# StarLiteMain.net
KiCad netlist of a schematic drawn in EAGLE
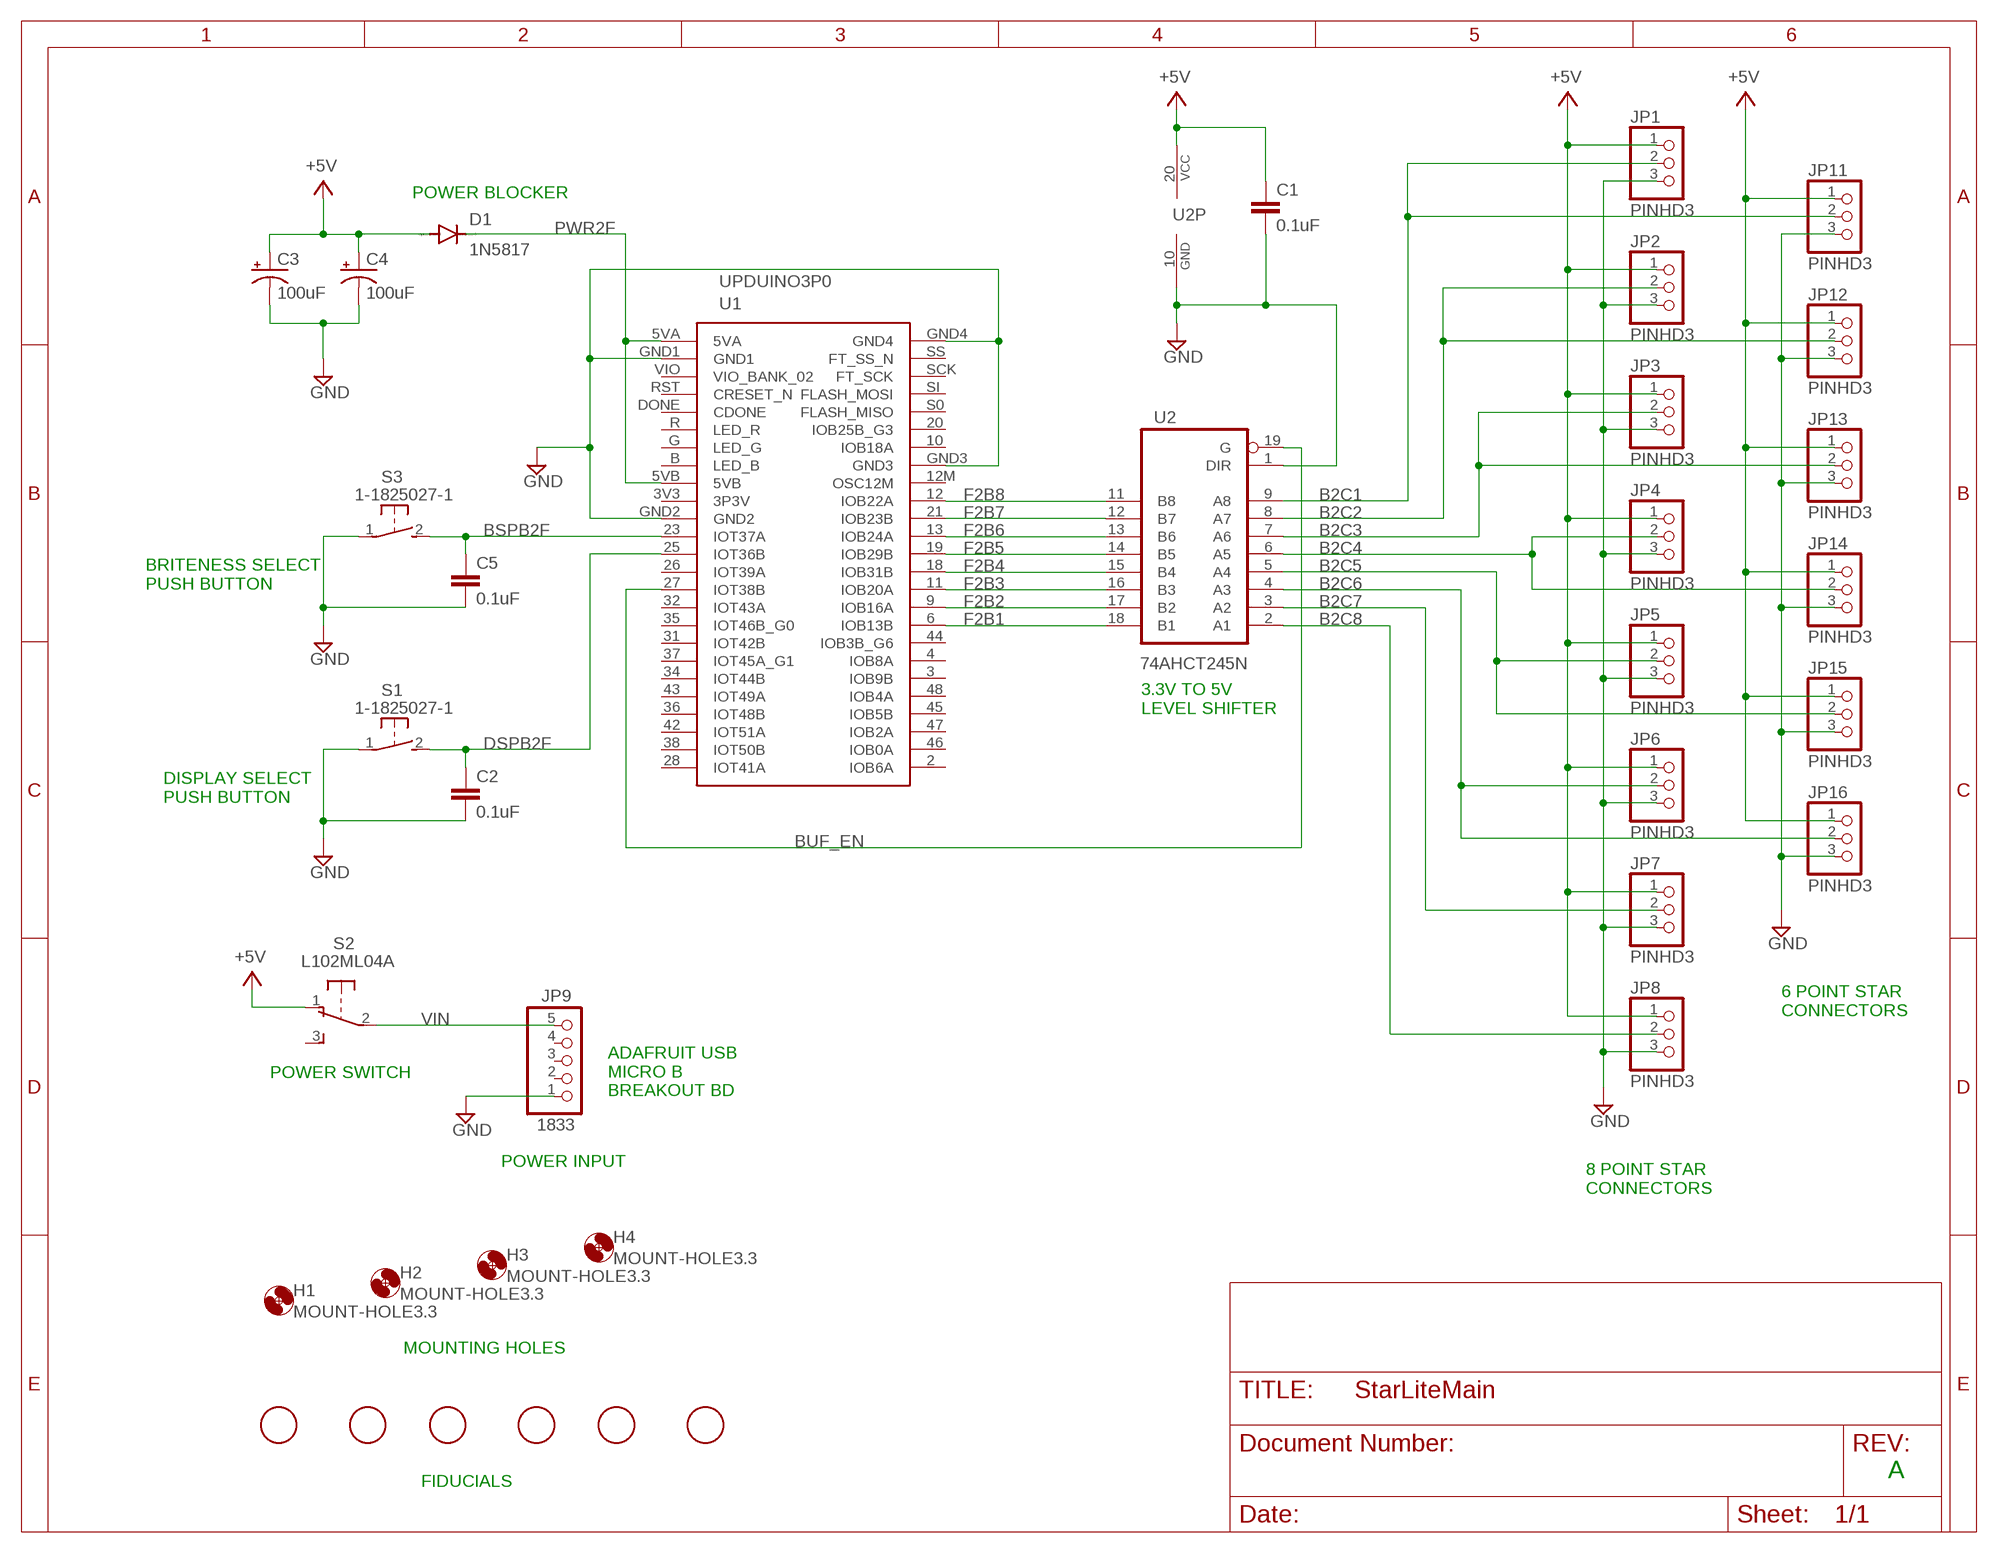
[diagram p0: schematic, sheet 1]

(export (version "E")
  (design (tool "Eeschema 10.0.6"))
  (components
    (comp (ref "C1")
      (value "0.1uF")
      (footprint "eagle-import:C2.5-3")
      (libsource (lib "eagle-import") (part "C2,5-3"))
    )
    (comp (ref "C2")
      (value "0.1uF")
      (footprint "eagle-import:C2.5-3")
      (libsource (lib "eagle-import") (part "C2,5-3"))
    )
    (comp (ref "C3")
      (value "100uF")
      (footprint "eagle-import:E2,5-6")
      (libsource (lib "eagle-import") (part "CPOL-USE2.5-6"))
    )
    (comp (ref "C4")
      (value "100uF")
      (footprint "eagle-import:E2,5-6")
      (libsource (lib "eagle-import") (part "CPOL-USE2.5-6"))
    )
    (comp (ref "C5")
      (value "0.1uF")
      (footprint "eagle-import:C2.5-3")
      (libsource (lib "eagle-import") (part "C2,5-3"))
    )
    (comp (ref "D1")
      (value "1N5817")
      (footprint "eagle-import:DO41-10")
      (libsource (lib "eagle-import") (part "DIODE-DO41-10"))
    )
    (comp (ref "H1")
      (value "MOUNT-HOLE3.3")
      (footprint "eagle-import:3,3")
      (libsource (lib "eagle-import") (part "MOUNT-HOLE3.3"))
    )
    (comp (ref "H2")
      (value "MOUNT-HOLE3.3")
      (footprint "eagle-import:3,3")
      (libsource (lib "eagle-import") (part "MOUNT-HOLE3.3"))
    )
    (comp (ref "H3")
      (value "MOUNT-HOLE3.3")
      (footprint "eagle-import:3,3")
      (libsource (lib "eagle-import") (part "MOUNT-HOLE3.3"))
    )
    (comp (ref "H4")
      (value "MOUNT-HOLE3.3")
      (footprint "eagle-import:3,3")
      (libsource (lib "eagle-import") (part "MOUNT-HOLE3.3"))
    )
    (comp (ref "JP1")
      (value "PINHD3")
      (footprint "eagle-import:1X03_50MIL")
      (libsource (lib "eagle-import") (part "PINHD-1X31X03_50"))
    )
    (comp (ref "JP2")
      (value "PINHD3")
      (footprint "eagle-import:1X03_50MIL")
      (libsource (lib "eagle-import") (part "PINHD-1X31X03_50"))
    )
    (comp (ref "JP3")
      (value "PINHD3")
      (footprint "eagle-import:1X03_50MIL")
      (libsource (lib "eagle-import") (part "PINHD-1X31X03_50"))
    )
    (comp (ref "JP4")
      (value "PINHD3")
      (footprint "eagle-import:1X03_50MIL")
      (libsource (lib "eagle-import") (part "PINHD-1X31X03_50"))
    )
    (comp (ref "JP5")
      (value "PINHD3")
      (footprint "eagle-import:1X03_50MIL")
      (libsource (lib "eagle-import") (part "PINHD-1X31X03_50"))
    )
    (comp (ref "JP6")
      (value "PINHD3")
      (footprint "eagle-import:1X03_50MIL")
      (libsource (lib "eagle-import") (part "PINHD-1X31X03_50"))
    )
    (comp (ref "JP7")
      (value "PINHD3")
      (footprint "eagle-import:1X03_50MIL")
      (libsource (lib "eagle-import") (part "PINHD-1X31X03_50"))
    )
    (comp (ref "JP8")
      (value "PINHD3")
      (footprint "eagle-import:1X03_50MIL")
      (libsource (lib "eagle-import") (part "PINHD-1X31X03_50"))
    )
    (comp (ref "JP9")
      (value "1833")
      (footprint "eagle-import:1X05")
      (libsource (lib "eagle-import") (part "PINHD-1X5"))
    )
    (comp (ref "JP11")
      (value "PINHD3")
      (footprint "eagle-import:1X03_50MIL")
      (libsource (lib "eagle-import") (part "PINHD-1X31X03_50"))
    )
    (comp (ref "JP12")
      (value "PINHD3")
      (footprint "eagle-import:1X03_50MIL")
      (libsource (lib "eagle-import") (part "PINHD-1X31X03_50"))
    )
    (comp (ref "JP13")
      (value "PINHD3")
      (footprint "eagle-import:1X03_50MIL")
      (libsource (lib "eagle-import") (part "PINHD-1X31X03_50"))
    )
    (comp (ref "JP14")
      (value "PINHD3")
      (footprint "eagle-import:1X03_50MIL")
      (libsource (lib "eagle-import") (part "PINHD-1X31X03_50"))
    )
    (comp (ref "JP15")
      (value "PINHD3")
      (footprint "eagle-import:1X03_50MIL")
      (libsource (lib "eagle-import") (part "PINHD-1X31X03_50"))
    )
    (comp (ref "JP16")
      (value "PINHD3")
      (footprint "eagle-import:1X03_50MIL")
      (libsource (lib "eagle-import") (part "PINHD-1X31X03_50"))
    )
    (comp (ref "S1")
      (value "1-1825027-1")
      (footprint "eagle-import:B3F-31XX")
      (fields (field (name "MPN") "B3F-3100"))
      (libsource (lib "eagle-import") (part "31-XX"))
    )
    (comp (ref "S2")
      (value "L102ML04A")
      (footprint "eagle-import:SPDT187")
      (libsource (lib "eagle-import") (part "L102ML04A"))
    )
    (comp (ref "S3")
      (value "1-1825027-1")
      (footprint "eagle-import:B3F-31XX")
      (fields (field (name "MPN") "B3F-3100"))
      (libsource (lib "eagle-import") (part "31-XX"))
    )
    (comp (ref "U$1")
      (value "FIDUCIAL")
      (footprint "eagle-import:FIDUCIAL_1MM")
      (libsource (lib "eagle-import") (part "FIDUCIAL"))
    )
    (comp (ref "U$2")
      (value "FIDUCIAL")
      (footprint "eagle-import:FIDUCIAL_1MM")
      (libsource (lib "eagle-import") (part "FIDUCIAL"))
    )
    (comp (ref "U$3")
      (value "FIDUCIAL")
      (footprint "eagle-import:FIDUCIAL_1MM")
      (libsource (lib "eagle-import") (part "FIDUCIAL"))
    )
    (comp (ref "U$4")
      (value "FIDUCIAL")
      (footprint "eagle-import:FIDUCIAL_1MM")
      (libsource (lib "eagle-import") (part "FIDUCIAL"))
    )
    (comp (ref "U$5")
      (value "FIDUCIAL")
      (footprint "eagle-import:FIDUCIAL_1MM")
      (libsource (lib "eagle-import") (part "FIDUCIAL"))
    )
    (comp (ref "U$6")
      (value "FIDUCIAL")
      (footprint "eagle-import:FIDUCIAL_1MM")
      (libsource (lib "eagle-import") (part "FIDUCIAL"))
    )
    (comp (ref "U1")
      (value "UPDUINO3P0")
      (footprint "eagle-import:UPDUINO3P0")
      (libsource (lib "eagle-import") (part "UPDUINO3P0"))
    )
    (comp (ref "U2")
      (value "74AHCT245N")
      (footprint "eagle-import:DIL20")
      (libsource (lib "eagle-import") (part "74245NAHCT"))
    )
  )
  (nets
    (net (code "1") (name "+5V") (class "Default")
      (node (ref "C1") (pin "1") (pinfunction "1_1") (pintype "passive"))
      (node (ref "C3") (pin "+") (pinfunction "+_+") (pintype "passive"))
      (node (ref "C4") (pin "+") (pinfunction "+_+") (pintype "passive"))
      (node (ref "D1") (pin "A") (pinfunction "A_A") (pintype "passive"))
      (node (ref "JP1") (pin "1") (pinfunction "1_1") (pintype "passive"))
      (node (ref "JP11") (pin "1") (pinfunction "1_1") (pintype "passive"))
      (node (ref "JP12") (pin "1") (pinfunction "1_1") (pintype "passive"))
      (node (ref "JP13") (pin "1") (pinfunction "1_1") (pintype "passive"))
      (node (ref "JP14") (pin "1") (pinfunction "1_1") (pintype "passive"))
      (node (ref "JP15") (pin "1") (pinfunction "1_1") (pintype "passive"))
      (node (ref "JP16") (pin "1") (pinfunction "1_1") (pintype "passive"))
      (node (ref "JP2") (pin "1") (pinfunction "1_1") (pintype "passive"))
      (node (ref "JP3") (pin "1") (pinfunction "1_1") (pintype "passive"))
      (node (ref "JP4") (pin "1") (pinfunction "1_1") (pintype "passive"))
      (node (ref "JP5") (pin "1") (pinfunction "1_1") (pintype "passive"))
      (node (ref "JP6") (pin "1") (pinfunction "1_1") (pintype "passive"))
      (node (ref "JP7") (pin "1") (pinfunction "1_1") (pintype "passive"))
      (node (ref "JP8") (pin "1") (pinfunction "1_1") (pintype "passive"))
      (node (ref "S2") (pin "1") (pinfunction "O_1") (pintype "passive"))
      (node (ref "U2") (pin "20") (pinfunction "VCC_20") (pintype "power_in"))
    )
    (net (code "2") (name "/B2C1") (class "Default")
      (node (ref "JP1") (pin "2") (pinfunction "2_2") (pintype "passive"))
      (node (ref "JP11") (pin "2") (pinfunction "2_2") (pintype "passive"))
      (node (ref "U2") (pin "9") (pinfunction "A8_9") (pintype "bidirectional"))
    )
    (net (code "3") (name "/B2C2") (class "Default")
      (node (ref "JP12") (pin "2") (pinfunction "2_2") (pintype "passive"))
      (node (ref "JP2") (pin "2") (pinfunction "2_2") (pintype "passive"))
      (node (ref "U2") (pin "8") (pinfunction "A7_8") (pintype "bidirectional"))
    )
    (net (code "4") (name "/B2C3") (class "Default")
      (node (ref "JP13") (pin "2") (pinfunction "2_2") (pintype "passive"))
      (node (ref "JP3") (pin "2") (pinfunction "2_2") (pintype "passive"))
      (node (ref "U2") (pin "7") (pinfunction "A6_7") (pintype "bidirectional"))
    )
    (net (code "5") (name "/B2C4") (class "Default")
      (node (ref "JP14") (pin "2") (pinfunction "2_2") (pintype "passive"))
      (node (ref "JP4") (pin "2") (pinfunction "2_2") (pintype "passive"))
      (node (ref "U2") (pin "6") (pinfunction "A5_6") (pintype "bidirectional"))
    )
    (net (code "6") (name "/B2C5") (class "Default")
      (node (ref "JP15") (pin "2") (pinfunction "2_2") (pintype "passive"))
      (node (ref "JP5") (pin "2") (pinfunction "2_2") (pintype "passive"))
      (node (ref "U2") (pin "5") (pinfunction "A4_5") (pintype "bidirectional"))
    )
    (net (code "7") (name "/B2C6") (class "Default")
      (node (ref "JP16") (pin "2") (pinfunction "2_2") (pintype "passive"))
      (node (ref "JP6") (pin "2") (pinfunction "2_2") (pintype "passive"))
      (node (ref "U2") (pin "4") (pinfunction "A3_4") (pintype "bidirectional"))
    )
    (net (code "8") (name "/B2C7") (class "Default")
      (node (ref "JP7") (pin "2") (pinfunction "2_2") (pintype "passive"))
      (node (ref "U2") (pin "3") (pinfunction "A2_3") (pintype "bidirectional"))
    )
    (net (code "9") (name "/B2C8") (class "Default")
      (node (ref "JP8") (pin "2") (pinfunction "2_2") (pintype "passive"))
      (node (ref "U2") (pin "2") (pinfunction "A1_2") (pintype "bidirectional"))
    )
    (net (code "10") (name "/BSPB2F") (class "Default")
      (node (ref "C5") (pin "1") (pinfunction "1_1") (pintype "passive"))
      (node (ref "S3") (pin "2") (pinfunction "S_2") (pintype "passive"))
      (node (ref "U1") (pin "23") (pinfunction "IOT37A_23") (pintype "bidirectional"))
    )
    (net (code "11") (name "/BUF_EN") (class "Default")
      (node (ref "U1") (pin "27") (pinfunction "IOT38B_27") (pintype "bidirectional"))
      (node (ref "U2") (pin "19") (pinfunction "G_19") (pintype "input"))
    )
    (net (code "12") (name "/DSPB2F") (class "Default")
      (node (ref "C2") (pin "1") (pinfunction "1_1") (pintype "passive"))
      (node (ref "S1") (pin "2") (pinfunction "S_2") (pintype "passive"))
      (node (ref "U1") (pin "25") (pinfunction "IOT36B_25") (pintype "bidirectional"))
    )
    (net (code "13") (name "/F2B1") (class "Default")
      (node (ref "U1") (pin "6") (pinfunction "IOB13B_6") (pintype "bidirectional"))
      (node (ref "U2") (pin "18") (pinfunction "B1_18") (pintype "bidirectional"))
    )
    (net (code "14") (name "/F2B2") (class "Default")
      (node (ref "U1") (pin "9") (pinfunction "IOB16A_9") (pintype "bidirectional"))
      (node (ref "U2") (pin "17") (pinfunction "B2_17") (pintype "bidirectional"))
    )
    (net (code "15") (name "/F2B3") (class "Default")
      (node (ref "U1") (pin "11") (pinfunction "IOB20A_11") (pintype "bidirectional"))
      (node (ref "U2") (pin "16") (pinfunction "B3_16") (pintype "bidirectional"))
    )
    (net (code "16") (name "/F2B4") (class "Default")
      (node (ref "U1") (pin "18") (pinfunction "IOB31B_18") (pintype "bidirectional"))
      (node (ref "U2") (pin "15") (pinfunction "B4_15") (pintype "bidirectional"))
    )
    (net (code "17") (name "/F2B5") (class "Default")
      (node (ref "U1") (pin "19") (pinfunction "IOB29B_19") (pintype "bidirectional"))
      (node (ref "U2") (pin "14") (pinfunction "B5_14") (pintype "bidirectional"))
    )
    (net (code "18") (name "/F2B6") (class "Default")
      (node (ref "U1") (pin "13") (pinfunction "IOB24A_13") (pintype "bidirectional"))
      (node (ref "U2") (pin "13") (pinfunction "B6_13") (pintype "bidirectional"))
    )
    (net (code "19") (name "/F2B7") (class "Default")
      (node (ref "U1") (pin "21") (pinfunction "IOB23B_21") (pintype "bidirectional"))
      (node (ref "U2") (pin "12") (pinfunction "B7_12") (pintype "bidirectional"))
    )
    (net (code "20") (name "/F2B8") (class "Default")
      (node (ref "U1") (pin "12") (pinfunction "IOB22A_12") (pintype "bidirectional"))
      (node (ref "U2") (pin "11") (pinfunction "B8_11") (pintype "bidirectional"))
    )
    (net (code "21") (name "/PWR2F") (class "Default")
      (node (ref "D1") (pin "C") (pinfunction "C_C") (pintype "passive"))
      (node (ref "U1") (pin "5VA") (pinfunction "5VA_5VA") (pintype "power_in"))
      (node (ref "U1") (pin "5VB") (pinfunction "5VB_5VB") (pintype "power_in"))
    )
    (net (code "22") (name "/VIN") (class "Default")
      (node (ref "JP9") (pin "5") (pinfunction "5_5") (pintype "passive"))
      (node (ref "S2") (pin "2") (pinfunction "P_2") (pintype "passive"))
    )
    (net (code "23") (name "GND") (class "Default")
      (node (ref "C1") (pin "2") (pinfunction "2_2") (pintype "passive"))
      (node (ref "C2") (pin "2") (pinfunction "2_2") (pintype "passive"))
      (node (ref "C3") (pin "-") (pinfunction "-_-") (pintype "passive"))
      (node (ref "C4") (pin "-") (pinfunction "-_-") (pintype "passive"))
      (node (ref "C5") (pin "2") (pinfunction "2_2") (pintype "passive"))
      (node (ref "JP1") (pin "3") (pinfunction "3_3") (pintype "passive"))
      (node (ref "JP11") (pin "3") (pinfunction "3_3") (pintype "passive"))
      (node (ref "JP12") (pin "3") (pinfunction "3_3") (pintype "passive"))
      (node (ref "JP13") (pin "3") (pinfunction "3_3") (pintype "passive"))
      (node (ref "JP14") (pin "3") (pinfunction "3_3") (pintype "passive"))
      (node (ref "JP15") (pin "3") (pinfunction "3_3") (pintype "passive"))
      (node (ref "JP16") (pin "3") (pinfunction "3_3") (pintype "passive"))
      (node (ref "JP2") (pin "3") (pinfunction "3_3") (pintype "passive"))
      (node (ref "JP3") (pin "3") (pinfunction "3_3") (pintype "passive"))
      (node (ref "JP4") (pin "3") (pinfunction "3_3") (pintype "passive"))
      (node (ref "JP5") (pin "3") (pinfunction "3_3") (pintype "passive"))
      (node (ref "JP6") (pin "3") (pinfunction "3_3") (pintype "passive"))
      (node (ref "JP7") (pin "3") (pinfunction "3_3") (pintype "passive"))
      (node (ref "JP8") (pin "3") (pinfunction "3_3") (pintype "passive"))
      (node (ref "JP9") (pin "1") (pinfunction "1_1") (pintype "passive"))
      (node (ref "S1") (pin "1") (pinfunction "P_1") (pintype "passive"))
      (node (ref "S3") (pin "1") (pinfunction "P_1") (pintype "passive"))
      (node (ref "U1") (pin "GND1") (pinfunction "GND1_GND1") (pintype "power_in"))
      (node (ref "U1") (pin "GND2") (pinfunction "GND2_GND2") (pintype "power_in"))
      (node (ref "U1") (pin "GND3") (pinfunction "GND3_GND3") (pintype "power_in"))
      (node (ref "U1") (pin "GND4") (pinfunction "GND4_GND4") (pintype "power_in"))
      (node (ref "U2") (pin "1") (pinfunction "DIR_1") (pintype "input"))
      (node (ref "U2") (pin "10") (pinfunction "GND_10") (pintype "power_in"))
    )
    (net (code "24") (name "unconnected-(JP9-Pad2)") (class "Default")
      (node (ref "JP9") (pin "2") (pinfunction "2_2") (pintype "passive"))
    )
    (net (code "25") (name "unconnected-(JP9-Pad3)") (class "Default")
      (node (ref "JP9") (pin "3") (pinfunction "3_3") (pintype "passive"))
    )
    (net (code "26") (name "unconnected-(JP9-Pad4)") (class "Default")
      (node (ref "JP9") (pin "4") (pinfunction "4_4") (pintype "passive"))
    )
    (net (code "27") (name "unconnected-(S2-S-Pad3)") (class "Default")
      (node (ref "S2") (pin "3") (pinfunction "S_3") (pintype "passive"))
    )
    (net (code "28") (name "unconnected-(U1-3P3V-Pad3V3)") (class "Default")
      (node (ref "U1") (pin "3V3") (pinfunction "3P3V_3V3") (pintype "passive"))
    )
    (net (code "29") (name "unconnected-(U1-CDONE-PadDONE)") (class "Default")
      (node (ref "U1") (pin "DONE") (pinfunction "CDONE_DONE") (pintype "bidirectional"))
    )
    (net (code "30") (name "unconnected-(U1-CRESET_N-PadRST)") (class "Default")
      (node (ref "U1") (pin "RST") (pinfunction "CRESET_N_RST") (pintype "bidirectional"))
    )
    (net (code "31") (name "unconnected-(U1-FLASH_MISO-PadS0)") (class "Default")
      (node (ref "U1") (pin "S0") (pinfunction "FLASH_MISO_S0") (pintype "bidirectional"))
    )
    (net (code "32") (name "unconnected-(U1-FLASH_MOSI-PadSI)") (class "Default")
      (node (ref "U1") (pin "SI") (pinfunction "FLASH_MOSI_SI") (pintype "bidirectional"))
    )
    (net (code "33") (name "unconnected-(U1-FT_SCK-PadSCK)") (class "Default")
      (node (ref "U1") (pin "SCK") (pinfunction "FT_SCK_SCK") (pintype "bidirectional"))
    )
    (net (code "34") (name "unconnected-(U1-FT_SS_N-PadSS)") (class "Default")
      (node (ref "U1") (pin "SS") (pinfunction "FT_SS_N_SS") (pintype "bidirectional"))
    )
    (net (code "35") (name "unconnected-(U1-IOB0A-Pad46)") (class "Default")
      (node (ref "U1") (pin "46") (pinfunction "IOB0A_46") (pintype "bidirectional"))
    )
    (net (code "36") (name "unconnected-(U1-IOB2A-Pad47)") (class "Default")
      (node (ref "U1") (pin "47") (pinfunction "IOB2A_47") (pintype "bidirectional"))
    )
    (net (code "37") (name "unconnected-(U1-IOB3B_G6-Pad44)") (class "Default")
      (node (ref "U1") (pin "44") (pinfunction "IOB3B_G6_44") (pintype "bidirectional"))
    )
    (net (code "38") (name "unconnected-(U1-IOB4A-Pad48)") (class "Default")
      (node (ref "U1") (pin "48") (pinfunction "IOB4A_48") (pintype "bidirectional"))
    )
    (net (code "39") (name "unconnected-(U1-IOB5B-Pad45)") (class "Default")
      (node (ref "U1") (pin "45") (pinfunction "IOB5B_45") (pintype "bidirectional"))
    )
    (net (code "40") (name "unconnected-(U1-IOB6A-Pad2)") (class "Default")
      (node (ref "U1") (pin "2") (pinfunction "IOB6A_2") (pintype "bidirectional"))
    )
    (net (code "41") (name "unconnected-(U1-IOB8A-Pad4)") (class "Default")
      (node (ref "U1") (pin "4") (pinfunction "IOB8A_4") (pintype "bidirectional"))
    )
    (net (code "42") (name "unconnected-(U1-IOB9B-Pad3)") (class "Default")
      (node (ref "U1") (pin "3") (pinfunction "IOB9B_3") (pintype "bidirectional"))
    )
    (net (code "43") (name "unconnected-(U1-IOB18A-Pad10)") (class "Default")
      (node (ref "U1") (pin "10") (pinfunction "IOB18A_10") (pintype "bidirectional"))
    )
    (net (code "44") (name "unconnected-(U1-IOB25B_G3-Pad20)") (class "Default")
      (node (ref "U1") (pin "20") (pinfunction "IOB25B_G3_20") (pintype "bidirectional"))
    )
    (net (code "45") (name "unconnected-(U1-IOT39A-Pad26)") (class "Default")
      (node (ref "U1") (pin "26") (pinfunction "IOT39A_26") (pintype "bidirectional"))
    )
    (net (code "46") (name "unconnected-(U1-IOT41A-Pad28)") (class "Default")
      (node (ref "U1") (pin "28") (pinfunction "IOT41A_28") (pintype "bidirectional"))
    )
    (net (code "47") (name "unconnected-(U1-IOT42B-Pad31)") (class "Default")
      (node (ref "U1") (pin "31") (pinfunction "IOT42B_31") (pintype "bidirectional"))
    )
    (net (code "48") (name "unconnected-(U1-IOT43A-Pad32)") (class "Default")
      (node (ref "U1") (pin "32") (pinfunction "IOT43A_32") (pintype "bidirectional"))
    )
    (net (code "49") (name "unconnected-(U1-IOT44B-Pad34)") (class "Default")
      (node (ref "U1") (pin "34") (pinfunction "IOT44B_34") (pintype "bidirectional"))
    )
    (net (code "50") (name "unconnected-(U1-IOT45A_G1-Pad37)") (class "Default")
      (node (ref "U1") (pin "37") (pinfunction "IOT45A_G1_37") (pintype "bidirectional"))
    )
    (net (code "51") (name "unconnected-(U1-IOT46B_G0-Pad35)") (class "Default")
      (node (ref "U1") (pin "35") (pinfunction "IOT46B_G0_35") (pintype "bidirectional"))
    )
    (net (code "52") (name "unconnected-(U1-IOT48B-Pad36)") (class "Default")
      (node (ref "U1") (pin "36") (pinfunction "IOT48B_36") (pintype "bidirectional"))
    )
    (net (code "53") (name "unconnected-(U1-IOT49A-Pad43)") (class "Default")
      (node (ref "U1") (pin "43") (pinfunction "IOT49A_43") (pintype "bidirectional"))
    )
    (net (code "54") (name "unconnected-(U1-IOT50B-Pad38)") (class "Default")
      (node (ref "U1") (pin "38") (pinfunction "IOT50B_38") (pintype "bidirectional"))
    )
    (net (code "55") (name "unconnected-(U1-IOT51A-Pad42)") (class "Default")
      (node (ref "U1") (pin "42") (pinfunction "IOT51A_42") (pintype "bidirectional"))
    )
    (net (code "56") (name "unconnected-(U1-LED_B-PadB)") (class "Default")
      (node (ref "U1") (pin "B") (pinfunction "LED_B_B") (pintype "bidirectional"))
    )
    (net (code "57") (name "unconnected-(U1-LED_G-PadG)") (class "Default")
      (node (ref "U1") (pin "G") (pinfunction "LED_G_G") (pintype "bidirectional"))
    )
    (net (code "58") (name "unconnected-(U1-LED_R-PadR)") (class "Default")
      (node (ref "U1") (pin "R") (pinfunction "LED_R_R") (pintype "bidirectional"))
    )
    (net (code "59") (name "unconnected-(U1-OSC12M-Pad12M)") (class "Default")
      (node (ref "U1") (pin "12M") (pinfunction "OSC12M_12M") (pintype "bidirectional"))
    )
    (net (code "60") (name "unconnected-(U1-VIO_BANK_02-PadVIO)") (class "Default")
      (node (ref "U1") (pin "VIO") (pinfunction "VIO_BANK_02_VIO") (pintype "bidirectional"))
    )
  )
)
